# Smart_Lid.net
KiCad netlist of a schematic drawn in EAGLE
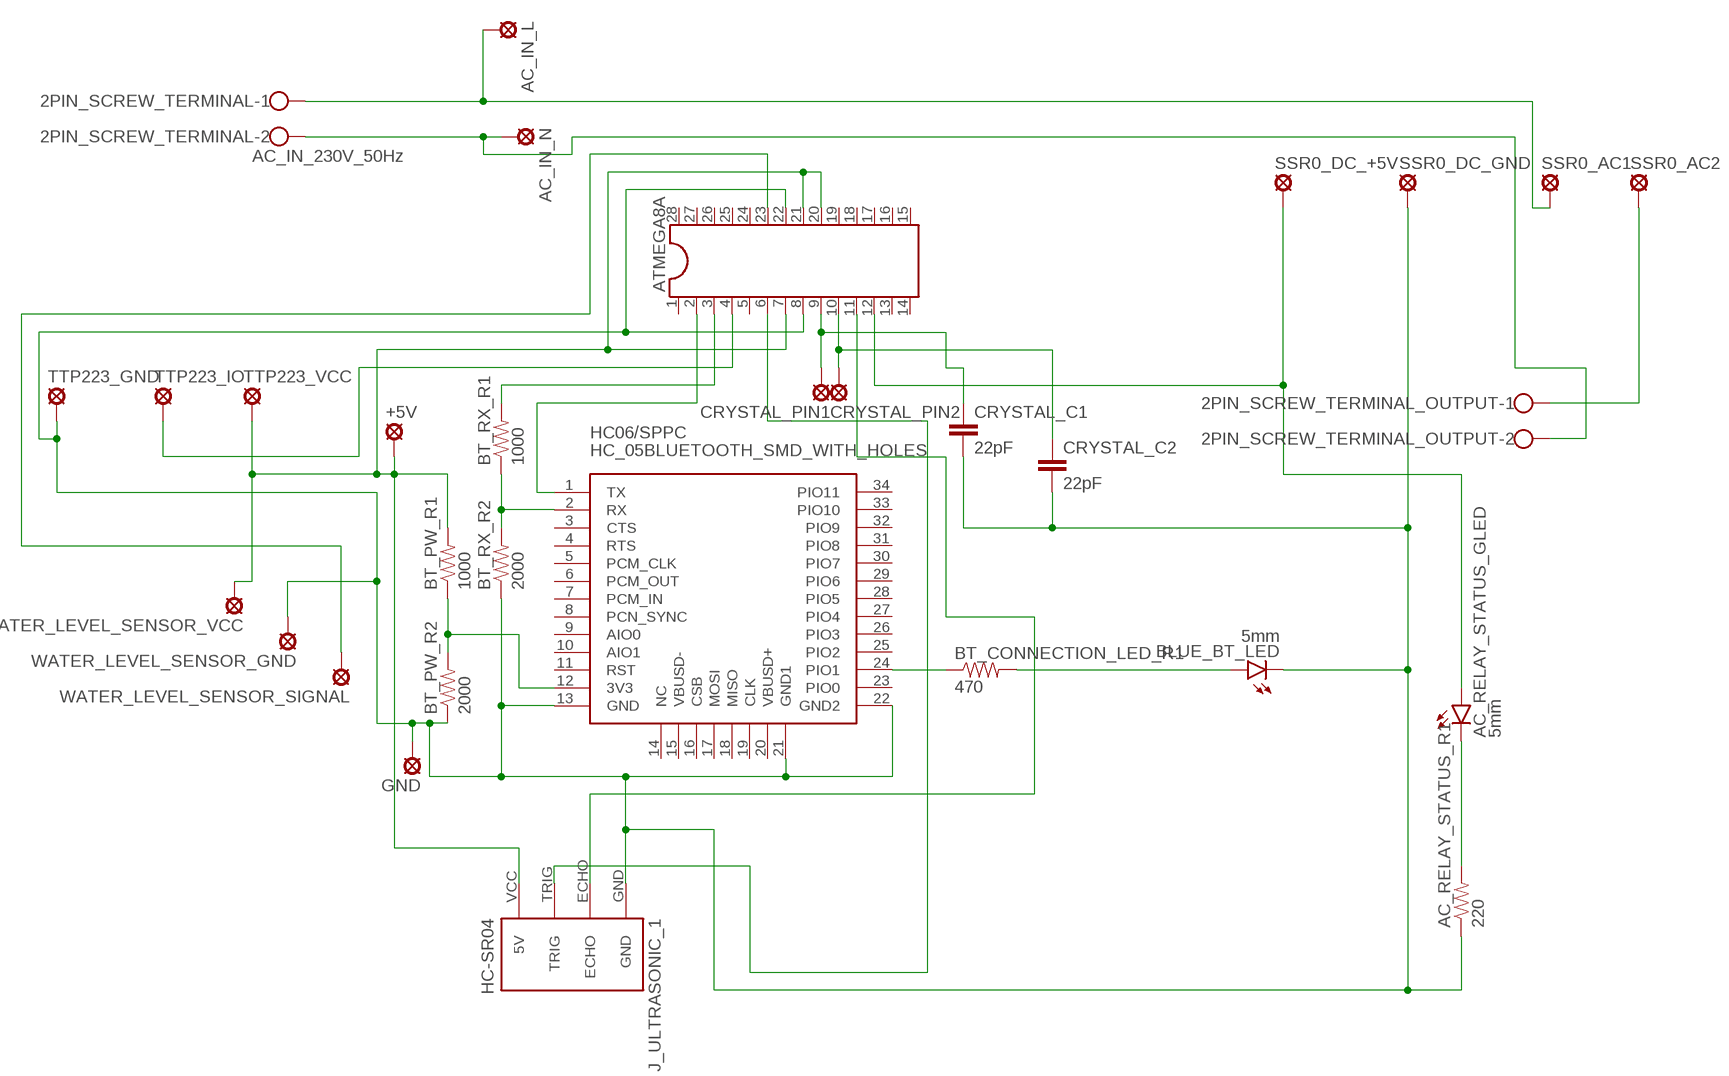
[diagram p0: schematic, sheet 1]

(export (version "E")
  (design (tool "Eeschema 10.0.6"))
  (components
    (comp (ref "+5V")
      (value "LSP10")
      (footprint "eagle-import:LSP10")
      (libsource (lib "eagle-import") (part "LSP10"))
    )
    (comp (ref "2PIN_SCREW_TERMINAL")
      (value "AC_IN_230V_50Hz")
      (footprint "eagle-import:W237-102")
      (fields (field (name "MPN") "237-102"))
      (libsource (lib "eagle-import") (part "W237-102"))
    )
    (comp (ref "2PIN_SCREW_TERMINAL_OUTPUT")
      (value "W237-102")
      (footprint "eagle-import:W237-102")
      (fields (field (name "MPN") "237-102"))
      (libsource (lib "eagle-import") (part "W237-102"))
    )
    (comp (ref "AC_IN_L")
      (value "LSP10")
      (footprint "eagle-import:LSP10")
      (libsource (lib "eagle-import") (part "LSP10"))
    )
    (comp (ref "AC_IN_N")
      (value "LSP10")
      (footprint "eagle-import:LSP10")
      (libsource (lib "eagle-import") (part "LSP10"))
    )
    (comp (ref "AC_RELAY_STATUS_GLED")
      (value "5mm")
      (footprint "eagle-import:LED5MM")
      (libsource (lib "eagle-import") (part "LED5MM"))
    )
    (comp (ref "AC_RELAY_STATUS_R1")
      (value "220")
      (footprint "eagle-import:1206")
      (libsource (lib "eagle-import") (part "RESISTOR1206"))
    )
    (comp (ref "ATMEGA8A")
      (value "DIL28DIL28-3_MODIFIED")
      (footprint "eagle-import:DIL28-3")
      (libsource (lib "eagle-import") (part "DIL28DIL28-3_MODIFIED"))
    )
    (comp (ref "BLUE_BT_LED")
      (value "5mm")
      (footprint "eagle-import:LED5MM")
      (libsource (lib "eagle-import") (part "LED5MM"))
    )
    (comp (ref "BT_CONNECTION_LED_R1")
      (value "470")
      (footprint "eagle-import:1206")
      (libsource (lib "eagle-import") (part "RESISTOR1206"))
    )
    (comp (ref "BT_PW_R1")
      (value "1000")
      (footprint "eagle-import:1206")
      (libsource (lib "eagle-import") (part "RESISTOR1206"))
    )
    (comp (ref "BT_PW_R2")
      (value "2000")
      (footprint "eagle-import:1206")
      (libsource (lib "eagle-import") (part "RESISTOR1206"))
    )
    (comp (ref "BT_RX_R1")
      (value "1000")
      (footprint "eagle-import:1206")
      (libsource (lib "eagle-import") (part "RESISTOR1206"))
    )
    (comp (ref "BT_RX_R2")
      (value "2000")
      (footprint "eagle-import:1206")
      (libsource (lib "eagle-import") (part "RESISTOR1206"))
    )
    (comp (ref "CRYSTAL_C1")
      (value "22pF")
      (footprint "eagle-import:1206")
      (libsource (lib "eagle-import") (part "CAP1206"))
    )
    (comp (ref "CRYSTAL_C2")
      (value "22pF")
      (footprint "eagle-import:1206")
      (libsource (lib "eagle-import") (part "CAP1206"))
    )
    (comp (ref "CRYSTAL_PIN1")
      (value "LSP10")
      (footprint "eagle-import:LSP10")
      (libsource (lib "eagle-import") (part "LSP10"))
    )
    (comp (ref "CRYSTAL_PIN2")
      (value "LSP10")
      (footprint "eagle-import:LSP10")
      (libsource (lib "eagle-import") (part "LSP10"))
    )
    (comp (ref "GND")
      (value "LSP10")
      (footprint "eagle-import:LSP10")
      (libsource (lib "eagle-import") (part "LSP10"))
    )
    (comp (ref "HC06/SPPC")
      (value "HC_05BLUETOOTH_SMD_WITH_HOLES")
      (footprint "eagle-import:BLUETOOTH_SMD")
      (libsource (lib "eagle-import") (part "HC_05BLUETOOTH_SMD_WITH_HOLES"))
    )
    (comp (ref "J_ULTRASONIC_1")
      (value "HC-SR04")
      (footprint "eagle-import:HC-SR04_FOOTPRINT")
      (libsource (lib "eagle-import") (part "HC-SR04"))
    )
    (comp (ref "SSR0_AC1")
      (value "LSP10")
      (footprint "eagle-import:LSP10")
      (libsource (lib "eagle-import") (part "LSP10"))
    )
    (comp (ref "SSR0_AC2")
      (value "LSP10")
      (footprint "eagle-import:LSP10")
      (libsource (lib "eagle-import") (part "LSP10"))
    )
    (comp (ref "SSR0_DC_+5V")
      (value "LSP10")
      (footprint "eagle-import:LSP10")
      (libsource (lib "eagle-import") (part "LSP10"))
    )
    (comp (ref "SSR0_DC_GND")
      (value "LSP10")
      (footprint "eagle-import:LSP10")
      (libsource (lib "eagle-import") (part "LSP10"))
    )
    (comp (ref "TTP223_GND")
      (value "LSP10")
      (footprint "eagle-import:LSP10")
      (libsource (lib "eagle-import") (part "LSP10"))
    )
    (comp (ref "TTP223_IO")
      (value "LSP10")
      (footprint "eagle-import:LSP10")
      (libsource (lib "eagle-import") (part "LSP10"))
    )
    (comp (ref "TTP223_VCC")
      (value "LSP10")
      (footprint "eagle-import:LSP10")
      (libsource (lib "eagle-import") (part "LSP10"))
    )
    (comp (ref "WATER_LEVEL_SENSOR_GND")
      (value "LSP10")
      (footprint "eagle-import:LSP10")
      (libsource (lib "eagle-import") (part "LSP10"))
    )
    (comp (ref "WATER_LEVEL_SENSOR_SIGNAL")
      (value "LSP10")
      (footprint "eagle-import:LSP10")
      (libsource (lib "eagle-import") (part "LSP10"))
    )
    (comp (ref "WATER_LEVEL_SENSOR_VCC")
      (value "LSP10")
      (footprint "eagle-import:LSP10")
      (libsource (lib "eagle-import") (part "LSP10"))
    )
  )
  (nets
    (net (code "1") (name "Net-(2PIN_SCREW_TERMINALA-KL)") (class "Default")
      (node (ref "2PIN_SCREW_TERMINAL") (pin "1") (pinfunction "KL_1") (pintype "passive"))
      (node (ref "AC_IN_L") (pin "MP") (pinfunction "MP_MP") (pintype "passive"))
      (node (ref "SSR0_AC1") (pin "MP") (pinfunction "MP_MP") (pintype "passive"))
    )
    (net (code "2") (name "Net-(2PIN_SCREW_TERMINALB-KL)") (class "Default")
      (node (ref "2PIN_SCREW_TERMINAL") (pin "2") (pinfunction "KL_2") (pintype "passive"))
      (node (ref "2PIN_SCREW_TERMINAL_OUTPUT") (pin "2") (pinfunction "KL_2") (pintype "passive"))
      (node (ref "AC_IN_N") (pin "MP") (pinfunction "MP_MP") (pintype "passive"))
    )
    (net (code "3") (name "Net-(2PIN_SCREW_TERMINAL_OUTPUTA-KL)") (class "Default")
      (node (ref "2PIN_SCREW_TERMINAL_OUTPUT") (pin "1") (pinfunction "KL_1") (pintype "passive"))
      (node (ref "SSR0_AC2") (pin "MP") (pinfunction "MP_MP") (pintype "passive"))
    )
    (net (code "4") (name "Net-(AC_RELAY_STATUS_GLED-C)") (class "Default")
      (node (ref "AC_RELAY_STATUS_GLED") (pin "K") (pinfunction "C_K") (pintype "passive"))
      (node (ref "AC_RELAY_STATUS_R1") (pin "2") (pinfunction "2_2") (pintype "passive"))
    )
    (net (code "5") (name "Net-(AC_RELAY_STATUS_GLED-PadA)") (class "Default")
      (node (ref "AC_RELAY_STATUS_GLED") (pin "A") (pinfunction "A_A") (pintype "passive"))
      (node (ref "ATMEGA8A") (pin "12") (pinfunction "12_12") (pintype "passive"))
      (node (ref "SSR0_DC_+5V") (pin "MP") (pinfunction "MP_MP") (pintype "passive"))
    )
    (net (code "6") (name "Net-(ATMEGA8A-Pad3)") (class "Default")
      (node (ref "ATMEGA8A") (pin "3") (pinfunction "3_3") (pintype "passive"))
      (node (ref "BT_RX_R1") (pin "2") (pinfunction "2_2") (pintype "passive"))
    )
    (net (code "7") (name "Net-(ATMEGA8A-Pad4)") (class "Default")
      (node (ref "ATMEGA8A") (pin "4") (pinfunction "4_4") (pintype "passive"))
      (node (ref "TTP223_IO") (pin "MP") (pinfunction "MP_MP") (pintype "passive"))
    )
    (net (code "8") (name "Net-(ATMEGA8A-Pad6)") (class "Default")
      (node (ref "ATMEGA8A") (pin "6") (pinfunction "6_6") (pintype "passive"))
      (node (ref "J_ULTRASONIC_1") (pin "TRIG") (pinfunction "TRIG_TRIG") (pintype "bidirectional"))
    )
    (net (code "9") (name "Net-(ATMEGA8A-Pad9)") (class "Default")
      (node (ref "ATMEGA8A") (pin "9") (pinfunction "9_9") (pintype "passive"))
      (node (ref "CRYSTAL_C1") (pin "1") (pinfunction "1_1") (pintype "passive"))
      (node (ref "CRYSTAL_PIN1") (pin "MP") (pinfunction "MP_MP") (pintype "passive"))
    )
    (net (code "10") (name "Net-(ATMEGA8A-Pad10)") (class "Default")
      (node (ref "ATMEGA8A") (pin "10") (pinfunction "10_10") (pintype "passive"))
      (node (ref "CRYSTAL_C2") (pin "1") (pinfunction "1_1") (pintype "passive"))
      (node (ref "CRYSTAL_PIN2") (pin "MP") (pinfunction "MP_MP") (pintype "passive"))
    )
    (net (code "11") (name "Net-(ATMEGA8A-Pad11)") (class "Default")
      (node (ref "ATMEGA8A") (pin "11") (pinfunction "11_11") (pintype "passive"))
      (node (ref "J_ULTRASONIC_1") (pin "ECHO") (pinfunction "ECHO_ECHO") (pintype "bidirectional"))
    )
    (net (code "12") (name "Net-(ATMEGA8A-Pad23)") (class "Default")
      (node (ref "ATMEGA8A") (pin "23") (pinfunction "23_23") (pintype "passive"))
      (node (ref "WATER_LEVEL_SENSOR_SIGNAL") (pin "MP") (pinfunction "MP_MP") (pintype "passive"))
    )
    (net (code "13") (name "Net-(BLUE_BT_LED-C)") (class "Default")
      (node (ref "AC_RELAY_STATUS_R1") (pin "1") (pinfunction "1_1") (pintype "passive"))
      (node (ref "ATMEGA8A") (pin "22") (pinfunction "22_22") (pintype "passive"))
      (node (ref "ATMEGA8A") (pin "8") (pinfunction "8_8") (pintype "passive"))
      (node (ref "BLUE_BT_LED") (pin "K") (pinfunction "C_K") (pintype "passive"))
      (node (ref "BT_PW_R2") (pin "1") (pinfunction "1_1") (pintype "passive"))
      (node (ref "BT_RX_R2") (pin "1") (pinfunction "1_1") (pintype "passive"))
      (node (ref "CRYSTAL_C1") (pin "2") (pinfunction "2_2") (pintype "passive"))
      (node (ref "CRYSTAL_C2") (pin "2") (pinfunction "2_2") (pintype "passive"))
      (node (ref "GND") (pin "MP") (pinfunction "MP_MP") (pintype "passive"))
      (node (ref "HC06/SPPC") (pin "13") (pinfunction "GND_13") (pintype "bidirectional"))
      (node (ref "HC06/SPPC") (pin "21") (pinfunction "GND1_21") (pintype "bidirectional"))
      (node (ref "HC06/SPPC") (pin "22") (pinfunction "GND2_22") (pintype "bidirectional"))
      (node (ref "J_ULTRASONIC_1") (pin "GND") (pinfunction "GND_GND") (pintype "bidirectional"))
      (node (ref "SSR0_DC_GND") (pin "MP") (pinfunction "MP_MP") (pintype "passive"))
      (node (ref "TTP223_GND") (pin "MP") (pinfunction "MP_MP") (pintype "passive"))
      (node (ref "WATER_LEVEL_SENSOR_GND") (pin "MP") (pinfunction "MP_MP") (pintype "passive"))
    )
    (net (code "14") (name "Net-(BLUE_BT_LED-PadA)") (class "Default")
      (node (ref "BLUE_BT_LED") (pin "A") (pinfunction "A_A") (pintype "passive"))
      (node (ref "BT_CONNECTION_LED_R1") (pin "2") (pinfunction "2_2") (pintype "passive"))
    )
    (net (code "15") (name "Net-(HC06/SPPC-3V3)") (class "Default")
      (node (ref "BT_PW_R1") (pin "1") (pinfunction "1_1") (pintype "passive"))
      (node (ref "BT_PW_R2") (pin "2") (pinfunction "2_2") (pintype "passive"))
      (node (ref "HC06/SPPC") (pin "12") (pinfunction "3V3_12") (pintype "bidirectional"))
    )
    (net (code "16") (name "Net-(HC06/SPPC-PIO1)") (class "Default")
      (node (ref "BT_CONNECTION_LED_R1") (pin "1") (pinfunction "1_1") (pintype "passive"))
      (node (ref "HC06/SPPC") (pin "24") (pinfunction "PIO1_24") (pintype "bidirectional"))
    )
    (net (code "17") (name "Net-(HC06/SPPC-RX)") (class "Default")
      (node (ref "BT_RX_R1") (pin "1") (pinfunction "1_1") (pintype "passive"))
      (node (ref "BT_RX_R2") (pin "2") (pinfunction "2_2") (pintype "passive"))
      (node (ref "HC06/SPPC") (pin "2") (pinfunction "RX_2") (pintype "bidirectional"))
    )
    (net (code "18") (name "Net-(HC06/SPPC-TX)") (class "Default")
      (node (ref "ATMEGA8A") (pin "2") (pinfunction "2_2") (pintype "passive"))
      (node (ref "HC06/SPPC") (pin "1") (pinfunction "TX_1") (pintype "bidirectional"))
    )
    (net (code "19") (name "Net-(J_ULTRASONIC_1-5V)") (class "Default")
      (node (ref "+5V") (pin "MP") (pinfunction "MP_MP") (pintype "passive"))
      (node (ref "ATMEGA8A") (pin "20") (pinfunction "20_20") (pintype "passive"))
      (node (ref "ATMEGA8A") (pin "21") (pinfunction "21_21") (pintype "passive"))
      (node (ref "ATMEGA8A") (pin "7") (pinfunction "7_7") (pintype "passive"))
      (node (ref "BT_PW_R1") (pin "2") (pinfunction "2_2") (pintype "passive"))
      (node (ref "J_ULTRASONIC_1") (pin "VCC") (pinfunction "5V_VCC") (pintype "bidirectional"))
      (node (ref "TTP223_VCC") (pin "MP") (pinfunction "MP_MP") (pintype "passive"))
      (node (ref "WATER_LEVEL_SENSOR_VCC") (pin "MP") (pinfunction "MP_MP") (pintype "passive"))
    )
    (net (code "20") (name "unconnected-(ATMEGA8A-Pad1)") (class "Default")
      (node (ref "ATMEGA8A") (pin "1") (pinfunction "1_1") (pintype "passive"))
    )
    (net (code "21") (name "unconnected-(ATMEGA8A-Pad5)") (class "Default")
      (node (ref "ATMEGA8A") (pin "5") (pinfunction "5_5") (pintype "passive"))
    )
    (net (code "22") (name "unconnected-(ATMEGA8A-Pad13)") (class "Default")
      (node (ref "ATMEGA8A") (pin "13") (pinfunction "13_13") (pintype "passive"))
    )
    (net (code "23") (name "unconnected-(ATMEGA8A-Pad14)") (class "Default")
      (node (ref "ATMEGA8A") (pin "14") (pinfunction "14_14") (pintype "passive"))
    )
    (net (code "24") (name "unconnected-(ATMEGA8A-Pad15)") (class "Default")
      (node (ref "ATMEGA8A") (pin "15") (pinfunction "15_15") (pintype "passive"))
    )
    (net (code "25") (name "unconnected-(ATMEGA8A-Pad16)") (class "Default")
      (node (ref "ATMEGA8A") (pin "16") (pinfunction "16_16") (pintype "passive"))
    )
    (net (code "26") (name "unconnected-(ATMEGA8A-Pad17)") (class "Default")
      (node (ref "ATMEGA8A") (pin "17") (pinfunction "17_17") (pintype "passive"))
    )
    (net (code "27") (name "unconnected-(ATMEGA8A-Pad18)") (class "Default")
      (node (ref "ATMEGA8A") (pin "18") (pinfunction "18_18") (pintype "passive"))
    )
    (net (code "28") (name "unconnected-(ATMEGA8A-Pad19)") (class "Default")
      (node (ref "ATMEGA8A") (pin "19") (pinfunction "19_19") (pintype "passive"))
    )
    (net (code "29") (name "unconnected-(ATMEGA8A-Pad24)") (class "Default")
      (node (ref "ATMEGA8A") (pin "24") (pinfunction "24_24") (pintype "passive"))
    )
    (net (code "30") (name "unconnected-(ATMEGA8A-Pad25)") (class "Default")
      (node (ref "ATMEGA8A") (pin "25") (pinfunction "25_25") (pintype "passive"))
    )
    (net (code "31") (name "unconnected-(ATMEGA8A-Pad26)") (class "Default")
      (node (ref "ATMEGA8A") (pin "26") (pinfunction "26_26") (pintype "passive"))
    )
    (net (code "32") (name "unconnected-(ATMEGA8A-Pad27)") (class "Default")
      (node (ref "ATMEGA8A") (pin "27") (pinfunction "27_27") (pintype "passive"))
    )
    (net (code "33") (name "unconnected-(ATMEGA8A-Pad28)") (class "Default")
      (node (ref "ATMEGA8A") (pin "28") (pinfunction "28_28") (pintype "passive"))
    )
    (net (code "34") (name "unconnected-(HC06/SPPC-AIO0-Pad9)") (class "Default")
      (node (ref "HC06/SPPC") (pin "9") (pinfunction "AIO0_9") (pintype "bidirectional"))
    )
    (net (code "35") (name "unconnected-(HC06/SPPC-AIO1-Pad10)") (class "Default")
      (node (ref "HC06/SPPC") (pin "10") (pinfunction "AIO1_10") (pintype "bidirectional"))
    )
    (net (code "36") (name "unconnected-(HC06/SPPC-CLK-Pad19)") (class "Default")
      (node (ref "HC06/SPPC") (pin "19") (pinfunction "CLK_19") (pintype "bidirectional"))
    )
    (net (code "37") (name "unconnected-(HC06/SPPC-CSB-Pad16)") (class "Default")
      (node (ref "HC06/SPPC") (pin "16") (pinfunction "CSB_16") (pintype "bidirectional"))
    )
    (net (code "38") (name "unconnected-(HC06/SPPC-CTS-Pad3)") (class "Default")
      (node (ref "HC06/SPPC") (pin "3") (pinfunction "CTS_3") (pintype "bidirectional"))
    )
    (net (code "39") (name "unconnected-(HC06/SPPC-MISO-Pad18)") (class "Default")
      (node (ref "HC06/SPPC") (pin "18") (pinfunction "MISO_18") (pintype "bidirectional"))
    )
    (net (code "40") (name "unconnected-(HC06/SPPC-MOSI-Pad17)") (class "Default")
      (node (ref "HC06/SPPC") (pin "17") (pinfunction "MOSI_17") (pintype "bidirectional"))
    )
    (net (code "41") (name "unconnected-(HC06/SPPC-NC-Pad14)") (class "Default")
      (node (ref "HC06/SPPC") (pin "14") (pinfunction "NC_14") (pintype "bidirectional"))
    )
    (net (code "42") (name "unconnected-(HC06/SPPC-PCM_CLK-Pad5)") (class "Default")
      (node (ref "HC06/SPPC") (pin "5") (pinfunction "PCM_CLK_5") (pintype "bidirectional"))
    )
    (net (code "43") (name "unconnected-(HC06/SPPC-PCM_IN-Pad7)") (class "Default")
      (node (ref "HC06/SPPC") (pin "7") (pinfunction "PCM_IN_7") (pintype "bidirectional"))
    )
    (net (code "44") (name "unconnected-(HC06/SPPC-PCM_OUT-Pad6)") (class "Default")
      (node (ref "HC06/SPPC") (pin "6") (pinfunction "PCM_OUT_6") (pintype "bidirectional"))
    )
    (net (code "45") (name "unconnected-(HC06/SPPC-PCN_SYNC-Pad8)") (class "Default")
      (node (ref "HC06/SPPC") (pin "8") (pinfunction "PCN_SYNC_8") (pintype "bidirectional"))
    )
    (net (code "46") (name "unconnected-(HC06/SPPC-PIO0-Pad23)") (class "Default")
      (node (ref "HC06/SPPC") (pin "23") (pinfunction "PIO0_23") (pintype "bidirectional"))
    )
    (net (code "47") (name "unconnected-(HC06/SPPC-PIO2-Pad25)") (class "Default")
      (node (ref "HC06/SPPC") (pin "25") (pinfunction "PIO2_25") (pintype "bidirectional"))
    )
    (net (code "48") (name "unconnected-(HC06/SPPC-PIO3-Pad26)") (class "Default")
      (node (ref "HC06/SPPC") (pin "26") (pinfunction "PIO3_26") (pintype "bidirectional"))
    )
    (net (code "49") (name "unconnected-(HC06/SPPC-PIO4-Pad27)") (class "Default")
      (node (ref "HC06/SPPC") (pin "27") (pinfunction "PIO4_27") (pintype "bidirectional"))
    )
    (net (code "50") (name "unconnected-(HC06/SPPC-PIO5-Pad28)") (class "Default")
      (node (ref "HC06/SPPC") (pin "28") (pinfunction "PIO5_28") (pintype "bidirectional"))
    )
    (net (code "51") (name "unconnected-(HC06/SPPC-PIO6-Pad29)") (class "Default")
      (node (ref "HC06/SPPC") (pin "29") (pinfunction "PIO6_29") (pintype "bidirectional"))
    )
    (net (code "52") (name "unconnected-(HC06/SPPC-PIO7-Pad30)") (class "Default")
      (node (ref "HC06/SPPC") (pin "30") (pinfunction "PIO7_30") (pintype "bidirectional"))
    )
    (net (code "53") (name "unconnected-(HC06/SPPC-PIO8-Pad31)") (class "Default")
      (node (ref "HC06/SPPC") (pin "31") (pinfunction "PIO8_31") (pintype "bidirectional"))
    )
    (net (code "54") (name "unconnected-(HC06/SPPC-PIO9-Pad32)") (class "Default")
      (node (ref "HC06/SPPC") (pin "32") (pinfunction "PIO9_32") (pintype "bidirectional"))
    )
    (net (code "55") (name "unconnected-(HC06/SPPC-PIO10-Pad33)") (class "Default")
      (node (ref "HC06/SPPC") (pin "33") (pinfunction "PIO10_33") (pintype "bidirectional"))
    )
    (net (code "56") (name "unconnected-(HC06/SPPC-PIO11-Pad34)") (class "Default")
      (node (ref "HC06/SPPC") (pin "34") (pinfunction "PIO11_34") (pintype "bidirectional"))
    )
    (net (code "57") (name "unconnected-(HC06/SPPC-RST-Pad11)") (class "Default")
      (node (ref "HC06/SPPC") (pin "11") (pinfunction "RST_11") (pintype "bidirectional"))
    )
    (net (code "58") (name "unconnected-(HC06/SPPC-RTS-Pad4)") (class "Default")
      (node (ref "HC06/SPPC") (pin "4") (pinfunction "RTS_4") (pintype "bidirectional"))
    )
    (net (code "59") (name "unconnected-(HC06/SPPC-VBUSD+-Pad20)") (class "Default")
      (node (ref "HC06/SPPC") (pin "20") (pinfunction "VBUSD+_20") (pintype "bidirectional"))
    )
    (net (code "60") (name "unconnected-(HC06/SPPC-VBUSD--Pad15)") (class "Default")
      (node (ref "HC06/SPPC") (pin "15") (pinfunction "VBUSD-_15") (pintype "bidirectional"))
    )
  )
)
